# ui.net
KiCad netlist of a schematic drawn in EAGLE
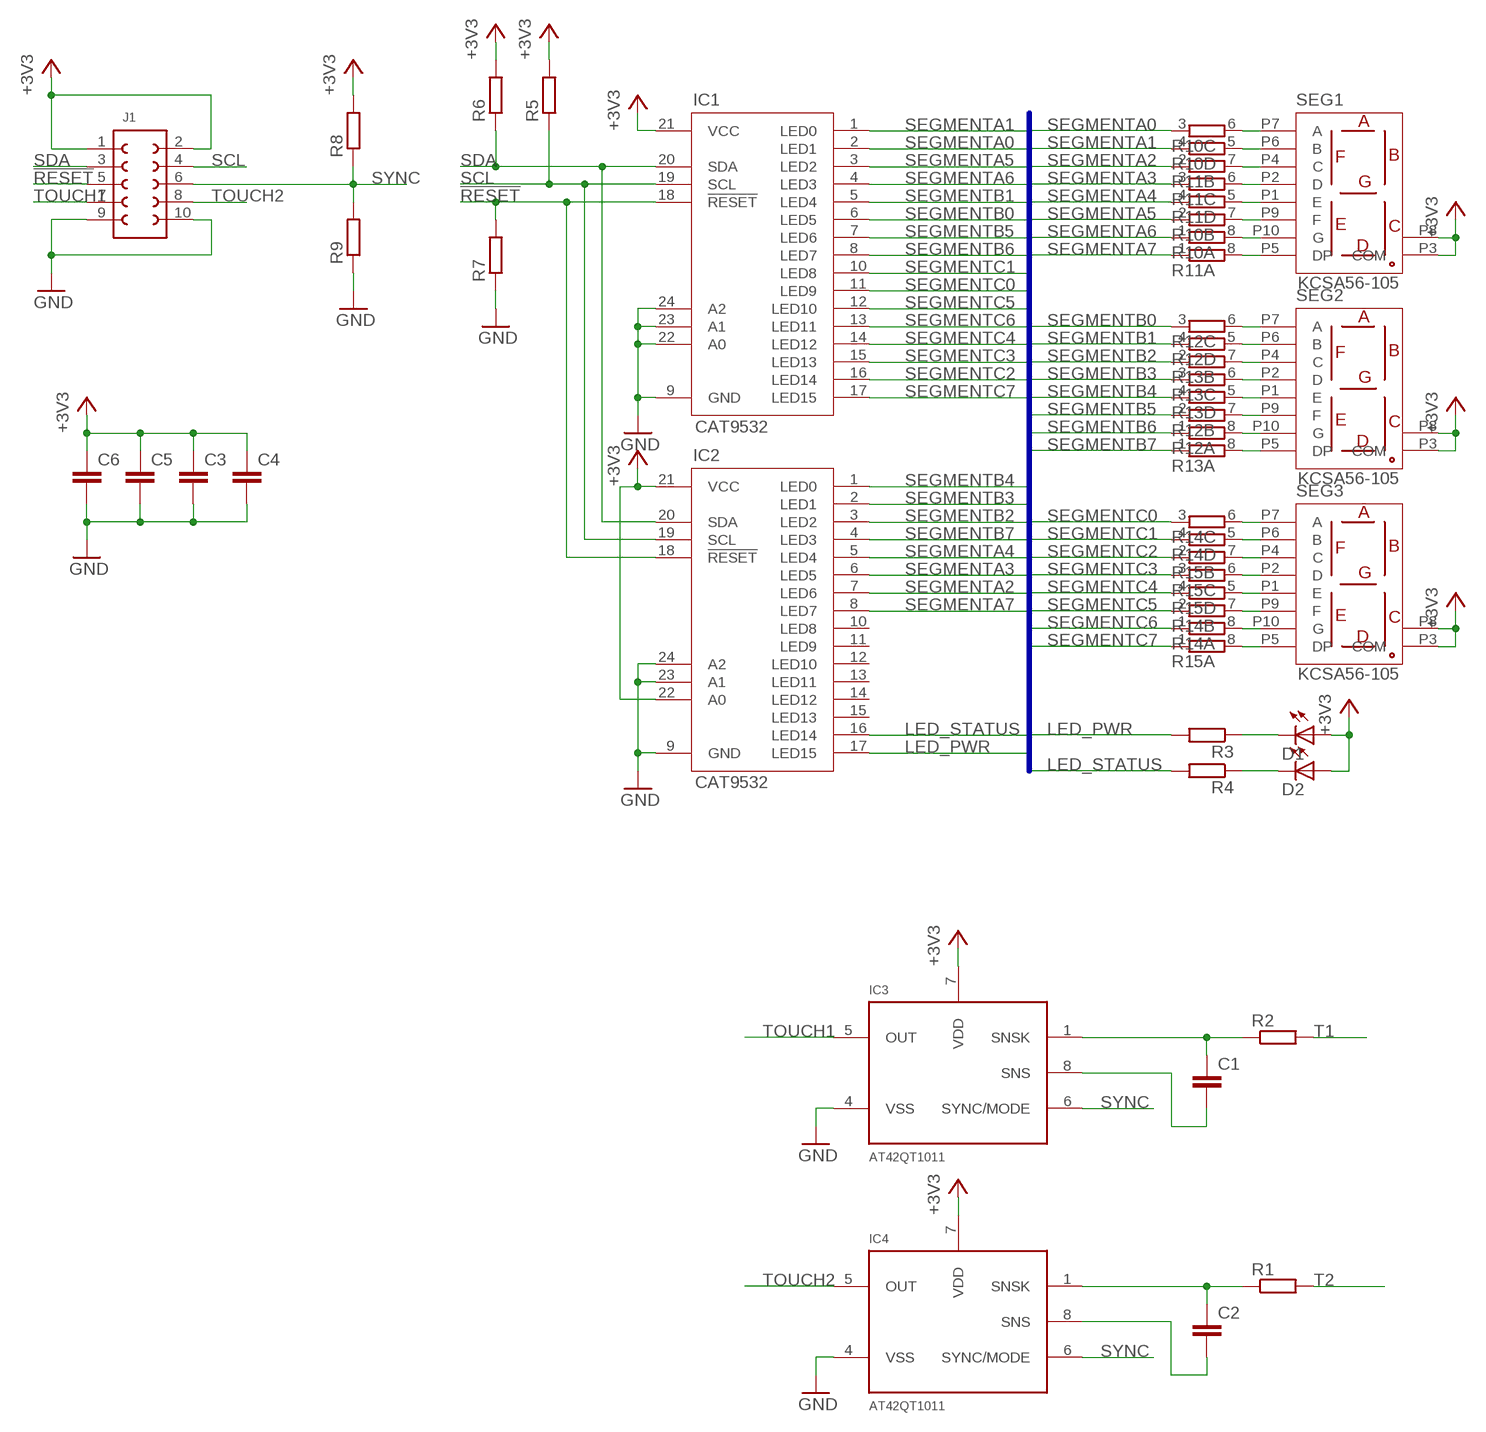
[diagram p0: schematic, sheet 1]

(export (version "E")
  (design (tool "Eeschema 10.0.6"))
  (components
    (comp (ref "C1")
      (value "C-EUC0603")
      (footprint "eagle-import:C0603")
      (libsource (lib "eagle-import") (part "C-EUC0603"))
    )
    (comp (ref "C2")
      (value "C-EUC0603")
      (footprint "eagle-import:C0603")
      (libsource (lib "eagle-import") (part "C-EUC0603"))
    )
    (comp (ref "C3")
      (value "C-EUC0603")
      (footprint "eagle-import:C0603")
      (libsource (lib "eagle-import") (part "C-EUC0603"))
    )
    (comp (ref "C4")
      (value "C-EUC0603")
      (footprint "eagle-import:C0603")
      (libsource (lib "eagle-import") (part "C-EUC0603"))
    )
    (comp (ref "C5")
      (value "C-EUC0603")
      (footprint "eagle-import:C0603")
      (libsource (lib "eagle-import") (part "C-EUC0603"))
    )
    (comp (ref "C6")
      (value "C-EUC0603")
      (footprint "eagle-import:C0603")
      (libsource (lib "eagle-import") (part "C-EUC0603"))
    )
    (comp (ref "D1")
      (value "KPTL-3216")
      (footprint "eagle-import:LED-REV")
      (libsource (lib "eagle-import") (part "KPTL-3216"))
    )
    (comp (ref "D2")
      (value "KPTL-3216")
      (footprint "eagle-import:LED-REV")
      (libsource (lib "eagle-import") (part "KPTL-3216"))
    )
    (comp (ref "IC1")
      (value "CAT9532")
      (footprint "eagle-import:TQFN24-EP")
      (libsource (lib "eagle-import") (part "CAT9532"))
    )
    (comp (ref "IC2")
      (value "CAT9532")
      (footprint "eagle-import:TQFN24-EP")
      (libsource (lib "eagle-import") (part "CAT9532"))
    )
    (comp (ref "IC3")
      (value "AT42QT1011")
      (footprint "eagle-import:UDFN_USON_8_PAD")
      (libsource (lib "eagle-import") (part "AT42QT1011"))
    )
    (comp (ref "IC4")
      (value "AT42QT1011")
      (footprint "eagle-import:UDFN_USON_8_PAD")
      (libsource (lib "eagle-import") (part "AT42QT1011"))
    )
    (comp (ref "J1")
      (value "610X1021121")
      (footprint "eagle-import:610X1021121")
      (libsource (lib "eagle-import") (part "610X1021121"))
    )
    (comp (ref "R1")
      (value "R-EU_R0603")
      (footprint "eagle-import:R0603")
      (libsource (lib "eagle-import") (part "R-EU_R0603"))
    )
    (comp (ref "R2")
      (value "R-EU_R0603")
      (footprint "eagle-import:R0603")
      (libsource (lib "eagle-import") (part "R-EU_R0603"))
    )
    (comp (ref "R3")
      (value "R-EU_R0603")
      (footprint "eagle-import:R0603")
      (libsource (lib "eagle-import") (part "R-EU_R0603"))
    )
    (comp (ref "R4")
      (value "R-EU_R0603")
      (footprint "eagle-import:R0603")
      (libsource (lib "eagle-import") (part "R-EU_R0603"))
    )
    (comp (ref "R5")
      (value "R-EU_R0603")
      (footprint "eagle-import:R0603")
      (libsource (lib "eagle-import") (part "R-EU_R0603"))
    )
    (comp (ref "R6")
      (value "R-EU_R0603")
      (footprint "eagle-import:R0603")
      (libsource (lib "eagle-import") (part "R-EU_R0603"))
    )
    (comp (ref "R7")
      (value "R-EU_R0603")
      (footprint "eagle-import:R0603")
      (libsource (lib "eagle-import") (part "R-EU_R0603"))
    )
    (comp (ref "R8")
      (value "R-EU_R0603")
      (footprint "eagle-import:R0603")
      (libsource (lib "eagle-import") (part "R-EU_R0603"))
    )
    (comp (ref "R9")
      (value "R-EU_R0603")
      (footprint "eagle-import:R0603")
      (libsource (lib "eagle-import") (part "R-EU_R0603"))
    )
    (comp (ref "R10")
      (value "4R-NCAT16")
      (footprint "eagle-import:CAT16")
      (libsource (lib "eagle-import") (part "4R-NCAT16"))
    )
    (comp (ref "R11")
      (value "4R-NCAT16")
      (footprint "eagle-import:CAT16")
      (libsource (lib "eagle-import") (part "4R-NCAT16"))
    )
    (comp (ref "R12")
      (value "4R-NCAT16")
      (footprint "eagle-import:CAT16")
      (libsource (lib "eagle-import") (part "4R-NCAT16"))
    )
    (comp (ref "R13")
      (value "4R-NCAT16")
      (footprint "eagle-import:CAT16")
      (libsource (lib "eagle-import") (part "4R-NCAT16"))
    )
    (comp (ref "R14")
      (value "4R-NCAT16")
      (footprint "eagle-import:CAT16")
      (libsource (lib "eagle-import") (part "4R-NCAT16"))
    )
    (comp (ref "R15")
      (value "4R-NCAT16")
      (footprint "eagle-import:CAT16")
      (libsource (lib "eagle-import") (part "4R-NCAT16"))
    )
    (comp (ref "SEG1")
      (value "KCSA56-105")
      (footprint "eagle-import:KCSA56-REV")
      (libsource (lib "eagle-import") (part "KCSA56-105"))
    )
    (comp (ref "SEG2")
      (value "KCSA56-105")
      (footprint "eagle-import:KCSA56-REV")
      (libsource (lib "eagle-import") (part "KCSA56-105"))
    )
    (comp (ref "SEG3")
      (value "KCSA56-105")
      (footprint "eagle-import:KCSA56-REV")
      (libsource (lib "eagle-import") (part "KCSA56-105"))
    )
  )
  (nets
    (net (code "1") (name "+3V3") (class "Default")
      (node (ref "C3") (pin "1") (pinfunction "1_1") (pintype "passive"))
      (node (ref "C4") (pin "1") (pinfunction "1_1") (pintype "passive"))
      (node (ref "C5") (pin "1") (pinfunction "1_1") (pintype "passive"))
      (node (ref "C6") (pin "1") (pinfunction "1_1") (pintype "passive"))
      (node (ref "D1") (pin "P$1") (pinfunction "A_P$1") (pintype "passive"))
      (node (ref "D2") (pin "P$1") (pinfunction "A_P$1") (pintype "passive"))
      (node (ref "IC1") (pin "21") (pinfunction "VCC_21") (pintype "bidirectional"))
      (node (ref "IC2") (pin "21") (pinfunction "VCC_21") (pintype "bidirectional"))
      (node (ref "IC2") (pin "22") (pinfunction "A0_22") (pintype "bidirectional"))
      (node (ref "IC3") (pin "7") (pinfunction "VDD_7") (pintype "bidirectional"))
      (node (ref "IC4") (pin "7") (pinfunction "VDD_7") (pintype "bidirectional"))
      (node (ref "J1") (pin "1") (pinfunction "1_1") (pintype "passive"))
      (node (ref "J1") (pin "2") (pinfunction "10_2") (pintype "passive"))
      (node (ref "R5") (pin "2") (pinfunction "2_2") (pintype "passive"))
      (node (ref "R6") (pin "2") (pinfunction "2_2") (pintype "passive"))
      (node (ref "R8") (pin "2") (pinfunction "2_2") (pintype "passive"))
      (node (ref "SEG1") (pin "P3") (pinfunction "COM_P3") (pintype "bidirectional"))
      (node (ref "SEG1") (pin "P8") (pintype "bidirectional"))
      (node (ref "SEG2") (pin "P3") (pinfunction "COM_P3") (pintype "bidirectional"))
      (node (ref "SEG2") (pin "P8") (pintype "bidirectional"))
      (node (ref "SEG3") (pin "P3") (pinfunction "COM_P3") (pintype "bidirectional"))
      (node (ref "SEG3") (pin "P8") (pintype "bidirectional"))
    )
    (net (code "2") (name "/LED_PWR") (class "Default")
      (node (ref "IC2") (pin "17") (pinfunction "LED15_17") (pintype "bidirectional"))
      (node (ref "R3") (pin "2") (pinfunction "2_2") (pintype "passive"))
    )
    (net (code "3") (name "/LED_STATUS") (class "Default")
      (node (ref "IC2") (pin "16") (pinfunction "LED14_16") (pintype "bidirectional"))
      (node (ref "R4") (pin "2") (pinfunction "2_2") (pintype "passive"))
    )
    (net (code "4") (name "/SCL") (class "Default")
      (node (ref "IC1") (pin "19") (pinfunction "SCL_19") (pintype "bidirectional"))
      (node (ref "IC2") (pin "19") (pinfunction "SCL_19") (pintype "bidirectional"))
      (node (ref "J1") (pin "4") (pinfunction "9_4") (pintype "passive"))
      (node (ref "R5") (pin "1") (pinfunction "1_1") (pintype "passive"))
    )
    (net (code "5") (name "/SDA") (class "Default")
      (node (ref "IC1") (pin "20") (pinfunction "SDA_20") (pintype "bidirectional"))
      (node (ref "IC2") (pin "20") (pinfunction "SDA_20") (pintype "bidirectional"))
      (node (ref "J1") (pin "3") (pinfunction "2_3") (pintype "passive"))
      (node (ref "R6") (pin "1") (pinfunction "1_1") (pintype "passive"))
    )
    (net (code "6") (name "/SEGMENTA0") (class "Default")
      (node (ref "IC1") (pin "2") (pinfunction "LED1_2") (pintype "bidirectional"))
      (node (ref "R10") (pin "3") (pinfunction "1_3") (pintype "passive"))
    )
    (net (code "7") (name "/SEGMENTA1") (class "Default")
      (node (ref "IC1") (pin "1") (pinfunction "LED0_1") (pintype "bidirectional"))
      (node (ref "R10") (pin "4") (pinfunction "1_4") (pintype "passive"))
    )
    (net (code "8") (name "/SEGMENTA2") (class "Default")
      (node (ref "IC2") (pin "7") (pinfunction "LED6_7") (pintype "bidirectional"))
      (node (ref "R11") (pin "2") (pinfunction "1_2") (pintype "passive"))
    )
    (net (code "9") (name "/SEGMENTA3") (class "Default")
      (node (ref "IC2") (pin "6") (pinfunction "LED5_6") (pintype "bidirectional"))
      (node (ref "R11") (pin "3") (pinfunction "1_3") (pintype "passive"))
    )
    (net (code "10") (name "/SEGMENTA4") (class "Default")
      (node (ref "IC2") (pin "5") (pinfunction "LED4_5") (pintype "bidirectional"))
      (node (ref "R11") (pin "4") (pinfunction "1_4") (pintype "passive"))
    )
    (net (code "11") (name "/SEGMENTA5") (class "Default")
      (node (ref "IC1") (pin "3") (pinfunction "LED2_3") (pintype "bidirectional"))
      (node (ref "R10") (pin "2") (pinfunction "1_2") (pintype "passive"))
    )
    (net (code "12") (name "/SEGMENTA6") (class "Default")
      (node (ref "IC1") (pin "4") (pinfunction "LED3_4") (pintype "bidirectional"))
      (node (ref "R10") (pin "1") (pinfunction "1_1") (pintype "passive"))
    )
    (net (code "13") (name "/SEGMENTA7") (class "Default")
      (node (ref "IC2") (pin "8") (pinfunction "LED7_8") (pintype "bidirectional"))
      (node (ref "R11") (pin "1") (pinfunction "1_1") (pintype "passive"))
    )
    (net (code "14") (name "/SEGMENTB0") (class "Default")
      (node (ref "IC1") (pin "6") (pinfunction "LED5_6") (pintype "bidirectional"))
      (node (ref "R12") (pin "3") (pinfunction "1_3") (pintype "passive"))
    )
    (net (code "15") (name "/SEGMENTB1") (class "Default")
      (node (ref "IC1") (pin "5") (pinfunction "LED4_5") (pintype "bidirectional"))
      (node (ref "R12") (pin "4") (pinfunction "1_4") (pintype "passive"))
    )
    (net (code "16") (name "/SEGMENTB2") (class "Default")
      (node (ref "IC2") (pin "3") (pinfunction "LED2_3") (pintype "bidirectional"))
      (node (ref "R13") (pin "2") (pinfunction "1_2") (pintype "passive"))
    )
    (net (code "17") (name "/SEGMENTB3") (class "Default")
      (node (ref "IC2") (pin "2") (pinfunction "LED1_2") (pintype "bidirectional"))
      (node (ref "R13") (pin "3") (pinfunction "1_3") (pintype "passive"))
    )
    (net (code "18") (name "/SEGMENTB4") (class "Default")
      (node (ref "IC2") (pin "1") (pinfunction "LED0_1") (pintype "bidirectional"))
      (node (ref "R13") (pin "4") (pinfunction "1_4") (pintype "passive"))
    )
    (net (code "19") (name "/SEGMENTB5") (class "Default")
      (node (ref "IC1") (pin "7") (pinfunction "LED6_7") (pintype "bidirectional"))
      (node (ref "R12") (pin "2") (pinfunction "1_2") (pintype "passive"))
    )
    (net (code "20") (name "/SEGMENTB6") (class "Default")
      (node (ref "IC1") (pin "8") (pinfunction "LED7_8") (pintype "bidirectional"))
      (node (ref "R12") (pin "1") (pinfunction "1_1") (pintype "passive"))
    )
    (net (code "21") (name "/SEGMENTB7") (class "Default")
      (node (ref "IC2") (pin "4") (pinfunction "LED3_4") (pintype "bidirectional"))
      (node (ref "R13") (pin "1") (pinfunction "1_1") (pintype "passive"))
    )
    (net (code "22") (name "/SEGMENTC0") (class "Default")
      (node (ref "IC1") (pin "11") (pinfunction "LED9_11") (pintype "bidirectional"))
      (node (ref "R14") (pin "3") (pinfunction "1_3") (pintype "passive"))
    )
    (net (code "23") (name "/SEGMENTC1") (class "Default")
      (node (ref "IC1") (pin "10") (pinfunction "LED8_10") (pintype "bidirectional"))
      (node (ref "R14") (pin "4") (pinfunction "1_4") (pintype "passive"))
    )
    (net (code "24") (name "/SEGMENTC2") (class "Default")
      (node (ref "IC1") (pin "16") (pinfunction "LED14_16") (pintype "bidirectional"))
      (node (ref "R15") (pin "2") (pinfunction "1_2") (pintype "passive"))
    )
    (net (code "25") (name "/SEGMENTC3") (class "Default")
      (node (ref "IC1") (pin "15") (pinfunction "LED13_15") (pintype "bidirectional"))
      (node (ref "R15") (pin "3") (pinfunction "1_3") (pintype "passive"))
    )
    (net (code "26") (name "/SEGMENTC4") (class "Default")
      (node (ref "IC1") (pin "14") (pinfunction "LED12_14") (pintype "bidirectional"))
      (node (ref "R15") (pin "4") (pinfunction "1_4") (pintype "passive"))
    )
    (net (code "27") (name "/SEGMENTC5") (class "Default")
      (node (ref "IC1") (pin "12") (pinfunction "LED10_12") (pintype "bidirectional"))
      (node (ref "R14") (pin "2") (pinfunction "1_2") (pintype "passive"))
    )
    (net (code "28") (name "/SEGMENTC6") (class "Default")
      (node (ref "IC1") (pin "13") (pinfunction "LED11_13") (pintype "bidirectional"))
      (node (ref "R14") (pin "1") (pinfunction "1_1") (pintype "passive"))
    )
    (net (code "29") (name "/SEGMENTC7") (class "Default")
      (node (ref "IC1") (pin "17") (pinfunction "LED15_17") (pintype "bidirectional"))
      (node (ref "R15") (pin "1") (pinfunction "1_1") (pintype "passive"))
    )
    (net (code "30") (name "/SYNC") (class "Default")
      (node (ref "IC3") (pin "6") (pinfunction "SYNC/MODE_6") (pintype "bidirectional"))
      (node (ref "IC4") (pin "6") (pinfunction "SYNC/MODE_6") (pintype "bidirectional"))
      (node (ref "J1") (pin "6") (pinfunction "8_6") (pintype "passive"))
      (node (ref "R8") (pin "1") (pinfunction "1_1") (pintype "passive"))
      (node (ref "R9") (pin "2") (pinfunction "2_2") (pintype "passive"))
    )
    (net (code "31") (name "/T1") (class "Default")
      (node (ref "R2") (pin "2") (pinfunction "2_2") (pintype "passive"))
    )
    (net (code "32") (name "/T2") (class "Default")
      (node (ref "R1") (pin "2") (pinfunction "2_2") (pintype "passive"))
    )
    (net (code "33") (name "/TOUCH1") (class "Default")
      (node (ref "IC3") (pin "5") (pinfunction "OUT_5") (pintype "bidirectional"))
      (node (ref "J1") (pin "7") (pinfunction "4_7") (pintype "passive"))
    )
    (net (code "34") (name "/TOUCH2") (class "Default")
      (node (ref "IC4") (pin "5") (pinfunction "OUT_5") (pintype "bidirectional"))
      (node (ref "J1") (pin "8") (pinfunction "7_8") (pintype "passive"))
    )
    (net (code "35") (name "/~{RESET}") (class "Default")
      (node (ref "IC1") (pin "18") (pinfunction "~{RESET}_18") (pintype "bidirectional"))
      (node (ref "IC2") (pin "18") (pinfunction "~{RESET}_18") (pintype "bidirectional"))
      (node (ref "J1") (pin "5") (pinfunction "3_5") (pintype "passive"))
      (node (ref "R7") (pin "2") (pinfunction "2_2") (pintype "passive"))
    )
    (net (code "36") (name "GND") (class "Default")
      (node (ref "C3") (pin "2") (pinfunction "2_2") (pintype "passive"))
      (node (ref "C4") (pin "2") (pinfunction "2_2") (pintype "passive"))
      (node (ref "C5") (pin "2") (pinfunction "2_2") (pintype "passive"))
      (node (ref "C6") (pin "2") (pinfunction "2_2") (pintype "passive"))
      (node (ref "IC1") (pin "22") (pinfunction "A0_22") (pintype "bidirectional"))
      (node (ref "IC1") (pin "23") (pinfunction "A1_23") (pintype "bidirectional"))
      (node (ref "IC1") (pin "24") (pinfunction "A2_24") (pintype "bidirectional"))
      (node (ref "IC1") (pin "9") (pinfunction "GND_9") (pintype "bidirectional"))
      (node (ref "IC2") (pin "23") (pinfunction "A1_23") (pintype "bidirectional"))
      (node (ref "IC2") (pin "24") (pinfunction "A2_24") (pintype "bidirectional"))
      (node (ref "IC2") (pin "9") (pinfunction "GND_9") (pintype "bidirectional"))
      (node (ref "IC3") (pin "4") (pinfunction "VSS_4") (pintype "bidirectional"))
      (node (ref "IC4") (pin "4") (pinfunction "VSS_4") (pintype "bidirectional"))
      (node (ref "J1") (pin "10") (pinfunction "6_10") (pintype "passive"))
      (node (ref "J1") (pin "9") (pinfunction "5_9") (pintype "passive"))
      (node (ref "R7") (pin "1") (pinfunction "1_1") (pintype "passive"))
      (node (ref "R9") (pin "1") (pinfunction "1_1") (pintype "passive"))
    )
    (net (code "37") (name "Net-(D1-C)") (class "Default")
      (node (ref "D1") (pin "P$2") (pinfunction "C_P$2") (pintype "passive"))
      (node (ref "R3") (pin "1") (pinfunction "1_1") (pintype "passive"))
    )
    (net (code "38") (name "Net-(D2-C)") (class "Default")
      (node (ref "D2") (pin "P$2") (pinfunction "C_P$2") (pintype "passive"))
      (node (ref "R4") (pin "1") (pinfunction "1_1") (pintype "passive"))
    )
    (net (code "39") (name "Net-(IC3-SNS)") (class "Default")
      (node (ref "C1") (pin "2") (pinfunction "2_2") (pintype "passive"))
      (node (ref "IC3") (pin "8") (pinfunction "SNS_8") (pintype "bidirectional"))
    )
    (net (code "40") (name "Net-(IC3-SNSK)") (class "Default")
      (node (ref "C1") (pin "1") (pinfunction "1_1") (pintype "passive"))
      (node (ref "IC3") (pin "1") (pinfunction "SNSK_1") (pintype "bidirectional"))
      (node (ref "R2") (pin "1") (pinfunction "1_1") (pintype "passive"))
    )
    (net (code "41") (name "Net-(IC4-SNS)") (class "Default")
      (node (ref "C2") (pin "2") (pinfunction "2_2") (pintype "passive"))
      (node (ref "IC4") (pin "8") (pinfunction "SNS_8") (pintype "bidirectional"))
    )
    (net (code "42") (name "Net-(IC4-SNSK)") (class "Default")
      (node (ref "C2") (pin "1") (pinfunction "1_1") (pintype "passive"))
      (node (ref "IC4") (pin "1") (pinfunction "SNSK_1") (pintype "bidirectional"))
      (node (ref "R1") (pin "1") (pinfunction "1_1") (pintype "passive"))
    )
    (net (code "43") (name "Net-(R10A-2)") (class "Default")
      (node (ref "R10") (pin "8") (pinfunction "2_8") (pintype "passive"))
      (node (ref "SEG1") (pin "P10") (pinfunction "G_P10") (pintype "bidirectional"))
    )
    (net (code "44") (name "Net-(R10B-2)") (class "Default")
      (node (ref "R10") (pin "7") (pinfunction "2_7") (pintype "passive"))
      (node (ref "SEG1") (pin "P9") (pinfunction "F_P9") (pintype "bidirectional"))
    )
    (net (code "45") (name "Net-(R10C-2)") (class "Default")
      (node (ref "R10") (pin "6") (pinfunction "2_6") (pintype "passive"))
      (node (ref "SEG1") (pin "P7") (pinfunction "A_P7") (pintype "bidirectional"))
    )
    (net (code "46") (name "Net-(R10D-2)") (class "Default")
      (node (ref "R10") (pin "5") (pinfunction "2_5") (pintype "passive"))
      (node (ref "SEG1") (pin "P6") (pinfunction "B_P6") (pintype "bidirectional"))
    )
    (net (code "47") (name "Net-(R11A-2)") (class "Default")
      (node (ref "R11") (pin "8") (pinfunction "2_8") (pintype "passive"))
      (node (ref "SEG1") (pin "P5") (pinfunction "DP_P5") (pintype "bidirectional"))
    )
    (net (code "48") (name "Net-(R11B-2)") (class "Default")
      (node (ref "R11") (pin "7") (pinfunction "2_7") (pintype "passive"))
      (node (ref "SEG1") (pin "P4") (pinfunction "C_P4") (pintype "bidirectional"))
    )
    (net (code "49") (name "Net-(R11C-2)") (class "Default")
      (node (ref "R11") (pin "6") (pinfunction "2_6") (pintype "passive"))
      (node (ref "SEG1") (pin "P2") (pinfunction "D_P2") (pintype "bidirectional"))
    )
    (net (code "50") (name "Net-(R11D-2)") (class "Default")
      (node (ref "R11") (pin "5") (pinfunction "2_5") (pintype "passive"))
      (node (ref "SEG1") (pin "P1") (pinfunction "E_P1") (pintype "bidirectional"))
    )
    (net (code "51") (name "Net-(R12A-2)") (class "Default")
      (node (ref "R12") (pin "8") (pinfunction "2_8") (pintype "passive"))
      (node (ref "SEG2") (pin "P10") (pinfunction "G_P10") (pintype "bidirectional"))
    )
    (net (code "52") (name "Net-(R12B-2)") (class "Default")
      (node (ref "R12") (pin "7") (pinfunction "2_7") (pintype "passive"))
      (node (ref "SEG2") (pin "P9") (pinfunction "F_P9") (pintype "bidirectional"))
    )
    (net (code "53") (name "Net-(R12C-2)") (class "Default")
      (node (ref "R12") (pin "6") (pinfunction "2_6") (pintype "passive"))
      (node (ref "SEG2") (pin "P7") (pinfunction "A_P7") (pintype "bidirectional"))
    )
    (net (code "54") (name "Net-(R12D-2)") (class "Default")
      (node (ref "R12") (pin "5") (pinfunction "2_5") (pintype "passive"))
      (node (ref "SEG2") (pin "P6") (pinfunction "B_P6") (pintype "bidirectional"))
    )
    (net (code "55") (name "Net-(R13A-2)") (class "Default")
      (node (ref "R13") (pin "8") (pinfunction "2_8") (pintype "passive"))
      (node (ref "SEG2") (pin "P5") (pinfunction "DP_P5") (pintype "bidirectional"))
    )
    (net (code "56") (name "Net-(R13B-2)") (class "Default")
      (node (ref "R13") (pin "7") (pinfunction "2_7") (pintype "passive"))
      (node (ref "SEG2") (pin "P4") (pinfunction "C_P4") (pintype "bidirectional"))
    )
    (net (code "57") (name "Net-(R13C-2)") (class "Default")
      (node (ref "R13") (pin "6") (pinfunction "2_6") (pintype "passive"))
      (node (ref "SEG2") (pin "P2") (pinfunction "D_P2") (pintype "bidirectional"))
    )
    (net (code "58") (name "Net-(R13D-2)") (class "Default")
      (node (ref "R13") (pin "5") (pinfunction "2_5") (pintype "passive"))
      (node (ref "SEG2") (pin "P1") (pinfunction "E_P1") (pintype "bidirectional"))
    )
    (net (code "59") (name "Net-(R14A-2)") (class "Default")
      (node (ref "R14") (pin "8") (pinfunction "2_8") (pintype "passive"))
      (node (ref "SEG3") (pin "P10") (pinfunction "G_P10") (pintype "bidirectional"))
    )
    (net (code "60") (name "Net-(R14B-2)") (class "Default")
      (node (ref "R14") (pin "7") (pinfunction "2_7") (pintype "passive"))
      (node (ref "SEG3") (pin "P9") (pinfunction "F_P9") (pintype "bidirectional"))
    )
    (net (code "61") (name "Net-(R14C-2)") (class "Default")
      (node (ref "R14") (pin "6") (pinfunction "2_6") (pintype "passive"))
      (node (ref "SEG3") (pin "P7") (pinfunction "A_P7") (pintype "bidirectional"))
    )
    (net (code "62") (name "Net-(R14D-2)") (class "Default")
      (node (ref "R14") (pin "5") (pinfunction "2_5") (pintype "passive"))
      (node (ref "SEG3") (pin "P6") (pinfunction "B_P6") (pintype "bidirectional"))
    )
    (net (code "63") (name "Net-(R15A-2)") (class "Default")
      (node (ref "R15") (pin "8") (pinfunction "2_8") (pintype "passive"))
      (node (ref "SEG3") (pin "P5") (pinfunction "DP_P5") (pintype "bidirectional"))
    )
    (net (code "64") (name "Net-(R15B-2)") (class "Default")
      (node (ref "R15") (pin "7") (pinfunction "2_7") (pintype "passive"))
      (node (ref "SEG3") (pin "P4") (pinfunction "C_P4") (pintype "bidirectional"))
    )
    (net (code "65") (name "Net-(R15C-2)") (class "Default")
      (node (ref "R15") (pin "6") (pinfunction "2_6") (pintype "passive"))
      (node (ref "SEG3") (pin "P2") (pinfunction "D_P2") (pintype "bidirectional"))
    )
    (net (code "66") (name "Net-(R15D-2)") (class "Default")
      (node (ref "R15") (pin "5") (pinfunction "2_5") (pintype "passive"))
      (node (ref "SEG3") (pin "P1") (pinfunction "E_P1") (pintype "bidirectional"))
    )
    (net (code "67") (name "unconnected-(IC2-LED8-Pad10)") (class "Default")
      (node (ref "IC2") (pin "10") (pinfunction "LED8_10") (pintype "bidirectional"))
    )
    (net (code "68") (name "unconnected-(IC2-LED9-Pad11)") (class "Default")
      (node (ref "IC2") (pin "11") (pinfunction "LED9_11") (pintype "bidirectional"))
    )
    (net (code "69") (name "unconnected-(IC2-LED10-Pad12)") (class "Default")
      (node (ref "IC2") (pin "12") (pinfunction "LED10_12") (pintype "bidirectional"))
    )
    (net (code "70") (name "unconnected-(IC2-LED11-Pad13)") (class "Default")
      (node (ref "IC2") (pin "13") (pinfunction "LED11_13") (pintype "bidirectional"))
    )
    (net (code "71") (name "unconnected-(IC2-LED12-Pad14)") (class "Default")
      (node (ref "IC2") (pin "14") (pinfunction "LED12_14") (pintype "bidirectional"))
    )
    (net (code "72") (name "unconnected-(IC2-LED13-Pad15)") (class "Default")
      (node (ref "IC2") (pin "15") (pinfunction "LED13_15") (pintype "bidirectional"))
    )
  )
)
